# Microcontroller.net
KiCad netlist of a schematic drawn in Altium Designer
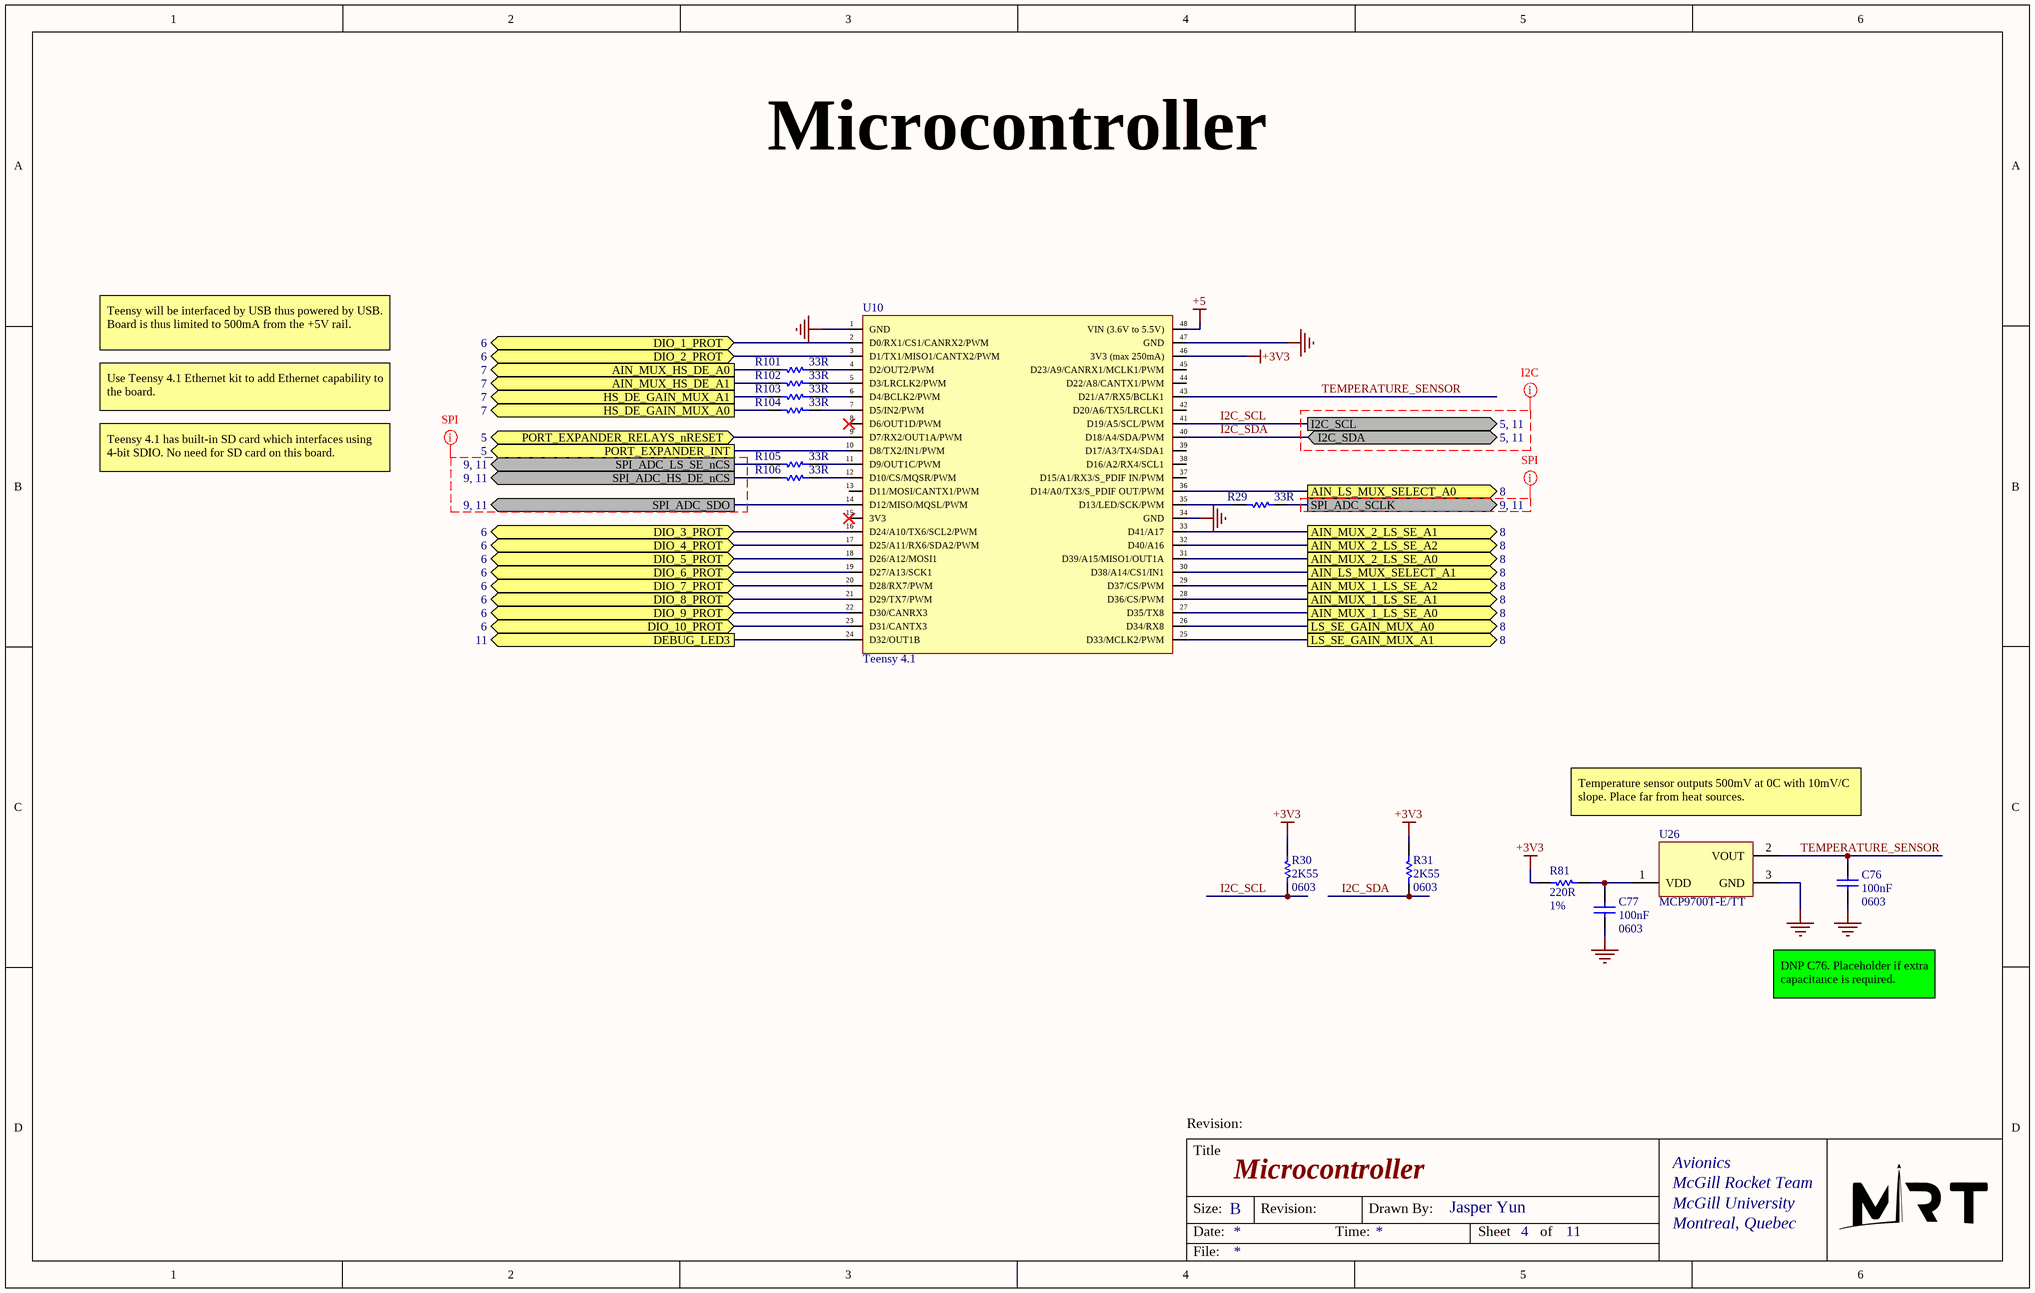
[diagram p0: Microcontroller.SchDoc]

(export (version "E")
  (design (tool "Eeschema 10.0.6"))
  (components
    (comp (ref "C76")
      (value "100nF")
      (footprint "0603 CAP SAMSUNG CL10C")
      (description "Capacitor")
      (fields (field (name "ALTIUM_VALUE") "0603") (field (name "PUBLISHER") "Altium Limited"))
      (libsource (lib "Miscellaneous Devices") (part "Cap"))
    )
    (comp (ref "C77")
      (value "100nF")
      (footprint "0603 CAP SAMSUNG CL10C")
      (description "Capacitor")
      (fields (field (name "ALTIUM_VALUE") "0603") (field (name "PUBLISHER") "Altium Limited"))
      (libsource (lib "Miscellaneous Devices") (part "Cap"))
    )
    (comp (ref "R29")
      (value "33R")
      (footprint "0603 RES")
      (description "Resistor")
      (fields (field (name "PUBLISHER") "Altium Limited"))
      (libsource (lib "Miscellaneous Devices") (part "Res1"))
    )
    (comp (ref "R30")
      (value "2K55")
      (footprint "0603 RES")
      (description "Resistor")
      (fields (field (name "ALTIUM_VALUE") "0603") (field (name "PUBLISHER") "Altium Limited"))
      (libsource (lib "Miscellaneous Devices") (part "Res1"))
    )
    (comp (ref "R31")
      (value "2K55")
      (footprint "0603 RES")
      (description "Resistor")
      (fields (field (name "ALTIUM_VALUE") "0603") (field (name "PUBLISHER") "Altium Limited"))
      (libsource (lib "Miscellaneous Devices") (part "Res1"))
    )
    (comp (ref "R81")
      (value "220R")
      (footprint "0603 RES")
      (description "Resistor")
      (fields (field (name "ALTIUM_VALUE") "1%") (field (name "PUBLISHER") "Altium Limited"))
      (libsource (lib "Miscellaneous Devices") (part "Res1"))
    )
    (comp (ref "R101")
      (value "33R")
      (footprint "0603 RES")
      (description "Resistor")
      (fields (field (name "PUBLISHER") "Altium Limited"))
      (libsource (lib "Miscellaneous Devices") (part "Res1"))
    )
    (comp (ref "R102")
      (value "33R")
      (footprint "0603 RES")
      (description "Resistor")
      (fields (field (name "PUBLISHER") "Altium Limited"))
      (libsource (lib "Miscellaneous Devices") (part "Res1"))
    )
    (comp (ref "R103")
      (value "33R")
      (footprint "0603 RES")
      (description "Resistor")
      (fields (field (name "PUBLISHER") "Altium Limited"))
      (libsource (lib "Miscellaneous Devices") (part "Res1"))
    )
    (comp (ref "R104")
      (value "33R")
      (footprint "0603 RES")
      (description "Resistor")
      (fields (field (name "PUBLISHER") "Altium Limited"))
      (libsource (lib "Miscellaneous Devices") (part "Res1"))
    )
    (comp (ref "R105")
      (value "33R")
      (footprint "0603 RES")
      (description "Resistor")
      (fields (field (name "PUBLISHER") "Altium Limited"))
      (libsource (lib "Miscellaneous Devices") (part "Res1"))
    )
    (comp (ref "R106")
      (value "33R")
      (footprint "0603 RES")
      (description "Resistor")
      (fields (field (name "PUBLISHER") "Altium Limited"))
      (libsource (lib "Miscellaneous Devices") (part "Res1"))
    )
    (comp (ref "U10")
      (value "Teensy 4.1")
      (footprint "Teensy 4.1")
      (description "Teensy 4.1 breakout (no ethernet or USB host pins exposed)")
      (libsource (lib "MRT SCH Library") (part "Teensy 4.1"))
    )
    (comp (ref "U26")
      (value "MCP9700T-E/TT")
      (footprint "SOT-23-TT3_M")
      (description "Low-Power Linear Active Thermistor IC, 3-Pin SOT-23, Extended Temperature, Tape and Reel")
      (libsource (lib "Altium Content Vault") (part "SEN-TEMP-MCP9700-3"))
    )
  )
  (nets
    (net (code "1") (name "+3V3") (class "Default")
      (node (ref "R30") (pin "1") (pinfunction "1_1") (pintype "passive"))
      (node (ref "R31") (pin "1") (pinfunction "1_1") (pintype "passive"))
      (node (ref "R81") (pin "1") (pinfunction "1_1") (pintype "passive"))
      (node (ref "U10") (pin "46") (pinfunction "3V3_(max_250mA)_46") (pintype "passive"))
    )
    (net (code "2") (name "+5") (class "Default")
      (node (ref "U10") (pin "48") (pinfunction "VIN_(3.6V_to_5.5V)_48") (pintype "passive"))
    )
    (net (code "3") (name "/AIN_LS_MUX_SELECT_A0") (class "Default")
      (node (ref "U10") (pin "36") (pinfunction "D14/A0/TX3/S_PDIF_OUT/PWM_36") (pintype "passive"))
    )
    (net (code "4") (name "/AIN_LS_MUX_SELECT_A1") (class "Default")
      (node (ref "U10") (pin "30") (pinfunction "D38/A14/CS1/IN1_30") (pintype "passive"))
    )
    (net (code "5") (name "/AIN_MUX_1_LS_SE_A0") (class "Default")
      (node (ref "U10") (pin "27") (pinfunction "D35/TX8_27") (pintype "passive"))
    )
    (net (code "6") (name "/AIN_MUX_1_LS_SE_A1") (class "Default")
      (node (ref "U10") (pin "28") (pinfunction "D36/CS/PWM_28") (pintype "passive"))
    )
    (net (code "7") (name "/AIN_MUX_1_LS_SE_A2") (class "Default")
      (node (ref "U10") (pin "29") (pinfunction "D37/CS/PWM_29") (pintype "passive"))
    )
    (net (code "8") (name "/AIN_MUX_2_LS_SE_A0") (class "Default")
      (node (ref "U10") (pin "31") (pinfunction "D39/A15/MISO1/OUT1A_31") (pintype "passive"))
    )
    (net (code "9") (name "/AIN_MUX_2_LS_SE_A1") (class "Default")
      (node (ref "U10") (pin "33") (pinfunction "D41/A17_33") (pintype "passive"))
    )
    (net (code "10") (name "/AIN_MUX_2_LS_SE_A2") (class "Default")
      (node (ref "U10") (pin "32") (pinfunction "D40/A16_32") (pintype "passive"))
    )
    (net (code "11") (name "/AIN_MUX_HS_DE_A0") (class "Default")
      (node (ref "R101") (pin "1") (pinfunction "1_1") (pintype "passive"))
    )
    (net (code "12") (name "/AIN_MUX_HS_DE_A1") (class "Default")
      (node (ref "R102") (pin "1") (pinfunction "1_1") (pintype "passive"))
    )
    (net (code "13") (name "/DEBUG_LED3") (class "Default")
      (node (ref "U10") (pin "24") (pinfunction "D32/OUT1B_24") (pintype "passive"))
    )
    (net (code "14") (name "/DIO_1_PROT") (class "Default")
      (node (ref "U10") (pin "2") (pinfunction "D0/RX1/CS1/CANRX2/PWM_2") (pintype "passive"))
    )
    (net (code "15") (name "/DIO_2_PROT") (class "Default")
      (node (ref "U10") (pin "3") (pinfunction "D1/TX1/MISO1/CANTX2/PWM_3") (pintype "passive"))
    )
    (net (code "16") (name "/DIO_3_PROT") (class "Default")
      (node (ref "U10") (pin "16") (pinfunction "D24/A10/TX6/SCL2/PWM_16") (pintype "passive"))
    )
    (net (code "17") (name "/DIO_4_PROT") (class "Default")
      (node (ref "U10") (pin "17") (pinfunction "D25/A11/RX6/SDA2/PWM_17") (pintype "passive"))
    )
    (net (code "18") (name "/DIO_5_PROT") (class "Default")
      (node (ref "U10") (pin "18") (pinfunction "D26/A12/MOSI1_18") (pintype "passive"))
    )
    (net (code "19") (name "/DIO_6_PROT") (class "Default")
      (node (ref "U10") (pin "19") (pinfunction "D27/A13/SCK1_19") (pintype "passive"))
    )
    (net (code "20") (name "/DIO_7_PROT") (class "Default")
      (node (ref "U10") (pin "20") (pinfunction "D28/RX7/PWM_20") (pintype "passive"))
    )
    (net (code "21") (name "/DIO_8_PROT") (class "Default")
      (node (ref "U10") (pin "21") (pinfunction "D29/TX7/PWM_21") (pintype "passive"))
    )
    (net (code "22") (name "/DIO_9_PROT") (class "Default")
      (node (ref "U10") (pin "22") (pinfunction "D30/CANRX3_22") (pintype "passive"))
    )
    (net (code "23") (name "/DIO_10_PROT") (class "Default")
      (node (ref "U10") (pin "23") (pinfunction "D31/CANTX3_23") (pintype "passive"))
    )
    (net (code "24") (name "/HS_DE_GAIN_MUX_A0") (class "Default")
      (node (ref "R104") (pin "1") (pinfunction "1_1") (pintype "passive"))
    )
    (net (code "25") (name "/HS_DE_GAIN_MUX_A1") (class "Default")
      (node (ref "R103") (pin "1") (pinfunction "1_1") (pintype "passive"))
    )
    (net (code "26") (name "/I2C_SCL") (class "Default")
      (node (ref "R30") (pin "2") (pinfunction "2_2") (pintype "passive"))
      (node (ref "U10") (pin "41") (pinfunction "D19/A5/SCL/PWM_41") (pintype "passive"))
    )
    (net (code "27") (name "/I2C_SDA") (class "Default")
      (node (ref "R31") (pin "2") (pinfunction "2_2") (pintype "passive"))
      (node (ref "U10") (pin "40") (pinfunction "D18/A4/SDA/PWM_40") (pintype "passive"))
    )
    (net (code "28") (name "/LS_SE_GAIN_MUX_A0") (class "Default")
      (node (ref "U10") (pin "26") (pinfunction "D34/RX8_26") (pintype "passive"))
    )
    (net (code "29") (name "/LS_SE_GAIN_MUX_A1") (class "Default")
      (node (ref "U10") (pin "25") (pinfunction "D33/MCLK2/PWM_25") (pintype "passive"))
    )
    (net (code "30") (name "/PORT_EXPANDER_INT") (class "Default")
      (node (ref "U10") (pin "10") (pinfunction "D8/TX2/IN1/PWM_10") (pintype "passive"))
    )
    (net (code "31") (name "/PORT_EXPANDER_RELAYS_nRESET") (class "Default")
      (node (ref "U10") (pin "9") (pinfunction "D7/RX2/OUT1A/PWM_9") (pintype "passive"))
    )
    (net (code "32") (name "/SPI_ADC_HS_DE_nCS") (class "Default")
      (node (ref "R106") (pin "1") (pinfunction "1_1") (pintype "passive"))
    )
    (net (code "33") (name "/SPI_ADC_LS_SE_nCS") (class "Default")
      (node (ref "R105") (pin "1") (pinfunction "1_1") (pintype "passive"))
    )
    (net (code "34") (name "/SPI_ADC_SCLK") (class "Default")
      (node (ref "R29") (pin "2") (pinfunction "2_2") (pintype "passive"))
    )
    (net (code "35") (name "/SPI_ADC_SDO") (class "Default")
      (node (ref "U10") (pin "14") (pinfunction "D12/MISO/MQSL/PWM_14") (pintype "passive"))
    )
    (net (code "36") (name "/TEMPERATURE_SENSOR") (class "Default")
      (node (ref "C76") (pin "2") (pinfunction "2_2") (pintype "passive"))
      (node (ref "U10") (pin "43") (pinfunction "D21/A7/RX5/BCLK1_43") (pintype "passive"))
      (node (ref "U26") (pin "2") (pinfunction "VOUT_2") (pintype "power_in"))
    )
    (net (code "37") (name "GND") (class "Default")
      (node (ref "C76") (pin "1") (pinfunction "1_1") (pintype "passive"))
      (node (ref "C77") (pin "1") (pinfunction "1_1") (pintype "passive"))
      (node (ref "U10") (pin "1") (pinfunction "GND_1") (pintype "passive"))
      (node (ref "U10") (pin "34") (pinfunction "GND_34") (pintype "passive"))
      (node (ref "U10") (pin "47") (pinfunction "GND_47") (pintype "passive"))
      (node (ref "U26") (pin "3") (pinfunction "GND_3") (pintype "power_in"))
    )
    (net (code "38") (name "Net-(U10-D2{slash}OUT2{slash}PWM)") (class "Default")
      (node (ref "R101") (pin "2") (pinfunction "2_2") (pintype "passive"))
      (node (ref "U10") (pin "4") (pinfunction "D2/OUT2/PWM_4") (pintype "passive"))
    )
    (net (code "39") (name "Net-(U10-D3{slash}LRCLK2{slash}PWM)") (class "Default")
      (node (ref "R102") (pin "2") (pinfunction "2_2") (pintype "passive"))
      (node (ref "U10") (pin "5") (pinfunction "D3/LRCLK2/PWM_5") (pintype "passive"))
    )
    (net (code "40") (name "Net-(U10-D4{slash}BCLK2{slash}PWM)") (class "Default")
      (node (ref "R103") (pin "2") (pinfunction "2_2") (pintype "passive"))
      (node (ref "U10") (pin "6") (pinfunction "D4/BCLK2/PWM_6") (pintype "passive"))
    )
    (net (code "41") (name "Net-(U10-D5{slash}IN2{slash}PWM)") (class "Default")
      (node (ref "R104") (pin "2") (pinfunction "2_2") (pintype "passive"))
      (node (ref "U10") (pin "7") (pinfunction "D5/IN2/PWM_7") (pintype "passive"))
    )
    (net (code "42") (name "Net-(U10-D9{slash}OUT1C{slash}PWM)") (class "Default")
      (node (ref "R105") (pin "2") (pinfunction "2_2") (pintype "passive"))
      (node (ref "U10") (pin "11") (pinfunction "D9/OUT1C/PWM_11") (pintype "passive"))
    )
    (net (code "43") (name "Net-(U10-D10{slash}CS{slash}MQSR{slash}PWM)") (class "Default")
      (node (ref "R106") (pin "2") (pinfunction "2_2") (pintype "passive"))
      (node (ref "U10") (pin "12") (pinfunction "D10/CS/MQSR/PWM_12") (pintype "passive"))
    )
    (net (code "44") (name "Net-(U10-D13{slash}LED{slash}SCK{slash}PWM)") (class "Default")
      (node (ref "R29") (pin "1") (pinfunction "1_1") (pintype "passive"))
      (node (ref "U10") (pin "35") (pinfunction "D13/LED/SCK/PWM_35") (pintype "passive"))
    )
    (net (code "45") (name "Net-(U26-VDD)") (class "Default")
      (node (ref "C77") (pin "2") (pinfunction "2_2") (pintype "passive"))
      (node (ref "R81") (pin "2") (pinfunction "2_2") (pintype "passive"))
      (node (ref "U26") (pin "1") (pinfunction "VDD_1") (pintype "power_in"))
    )
    (net (code "46") (name "unconnected-(U10-3V3-Pad15)") (class "Default")
      (node (ref "U10") (pin "15") (pinfunction "3V3_15") (pintype "passive+no_connect"))
    )
    (net (code "47") (name "unconnected-(U10-D6{slash}OUT1D{slash}PWM-Pad8)") (class "Default")
      (node (ref "U10") (pin "8") (pinfunction "D6/OUT1D/PWM_8") (pintype "passive+no_connect"))
    )
    (net (code "48") (name "unconnected-(U10-D11{slash}MOSI{slash}CANTX1{slash}PWM-Pad13)") (class "Default")
      (node (ref "U10") (pin "13") (pinfunction "D11/MOSI/CANTX1/PWM_13") (pintype "passive"))
    )
    (net (code "49") (name "unconnected-(U10-D15{slash}A1{slash}RX3{slash}S_PDIF_IN{slash}PWM-Pad37)") (class "Default")
      (node (ref "U10") (pin "37") (pinfunction "D15/A1/RX3/S_PDIF_IN/PWM_37") (pintype "passive"))
    )
    (net (code "50") (name "unconnected-(U10-D16{slash}A2{slash}RX4{slash}SCL1-Pad38)") (class "Default")
      (node (ref "U10") (pin "38") (pinfunction "D16/A2/RX4/SCL1_38") (pintype "passive"))
    )
    (net (code "51") (name "unconnected-(U10-D17{slash}A3{slash}TX4{slash}SDA1-Pad39)") (class "Default")
      (node (ref "U10") (pin "39") (pinfunction "D17/A3/TX4/SDA1_39") (pintype "passive"))
    )
    (net (code "52") (name "unconnected-(U10-D20{slash}A6{slash}TX5{slash}LRCLK1-Pad42)") (class "Default")
      (node (ref "U10") (pin "42") (pinfunction "D20/A6/TX5/LRCLK1_42") (pintype "passive"))
    )
    (net (code "53") (name "unconnected-(U10-D22{slash}A8{slash}CANTX1{slash}PWM-Pad44)") (class "Default")
      (node (ref "U10") (pin "44") (pinfunction "D22/A8/CANTX1/PWM_44") (pintype "passive"))
    )
    (net (code "54") (name "unconnected-(U10-D23{slash}A9{slash}CANRX1{slash}MCLK1{slash}PWM-Pad45)") (class "Default")
      (node (ref "U10") (pin "45") (pinfunction "D23/A9/CANRX1/MCLK1/PWM_45") (pintype "passive"))
    )
  )
)
